# Shruthi-Analog-Polivoks-v01.net
KiCad netlist of a schematic drawn in EAGLE
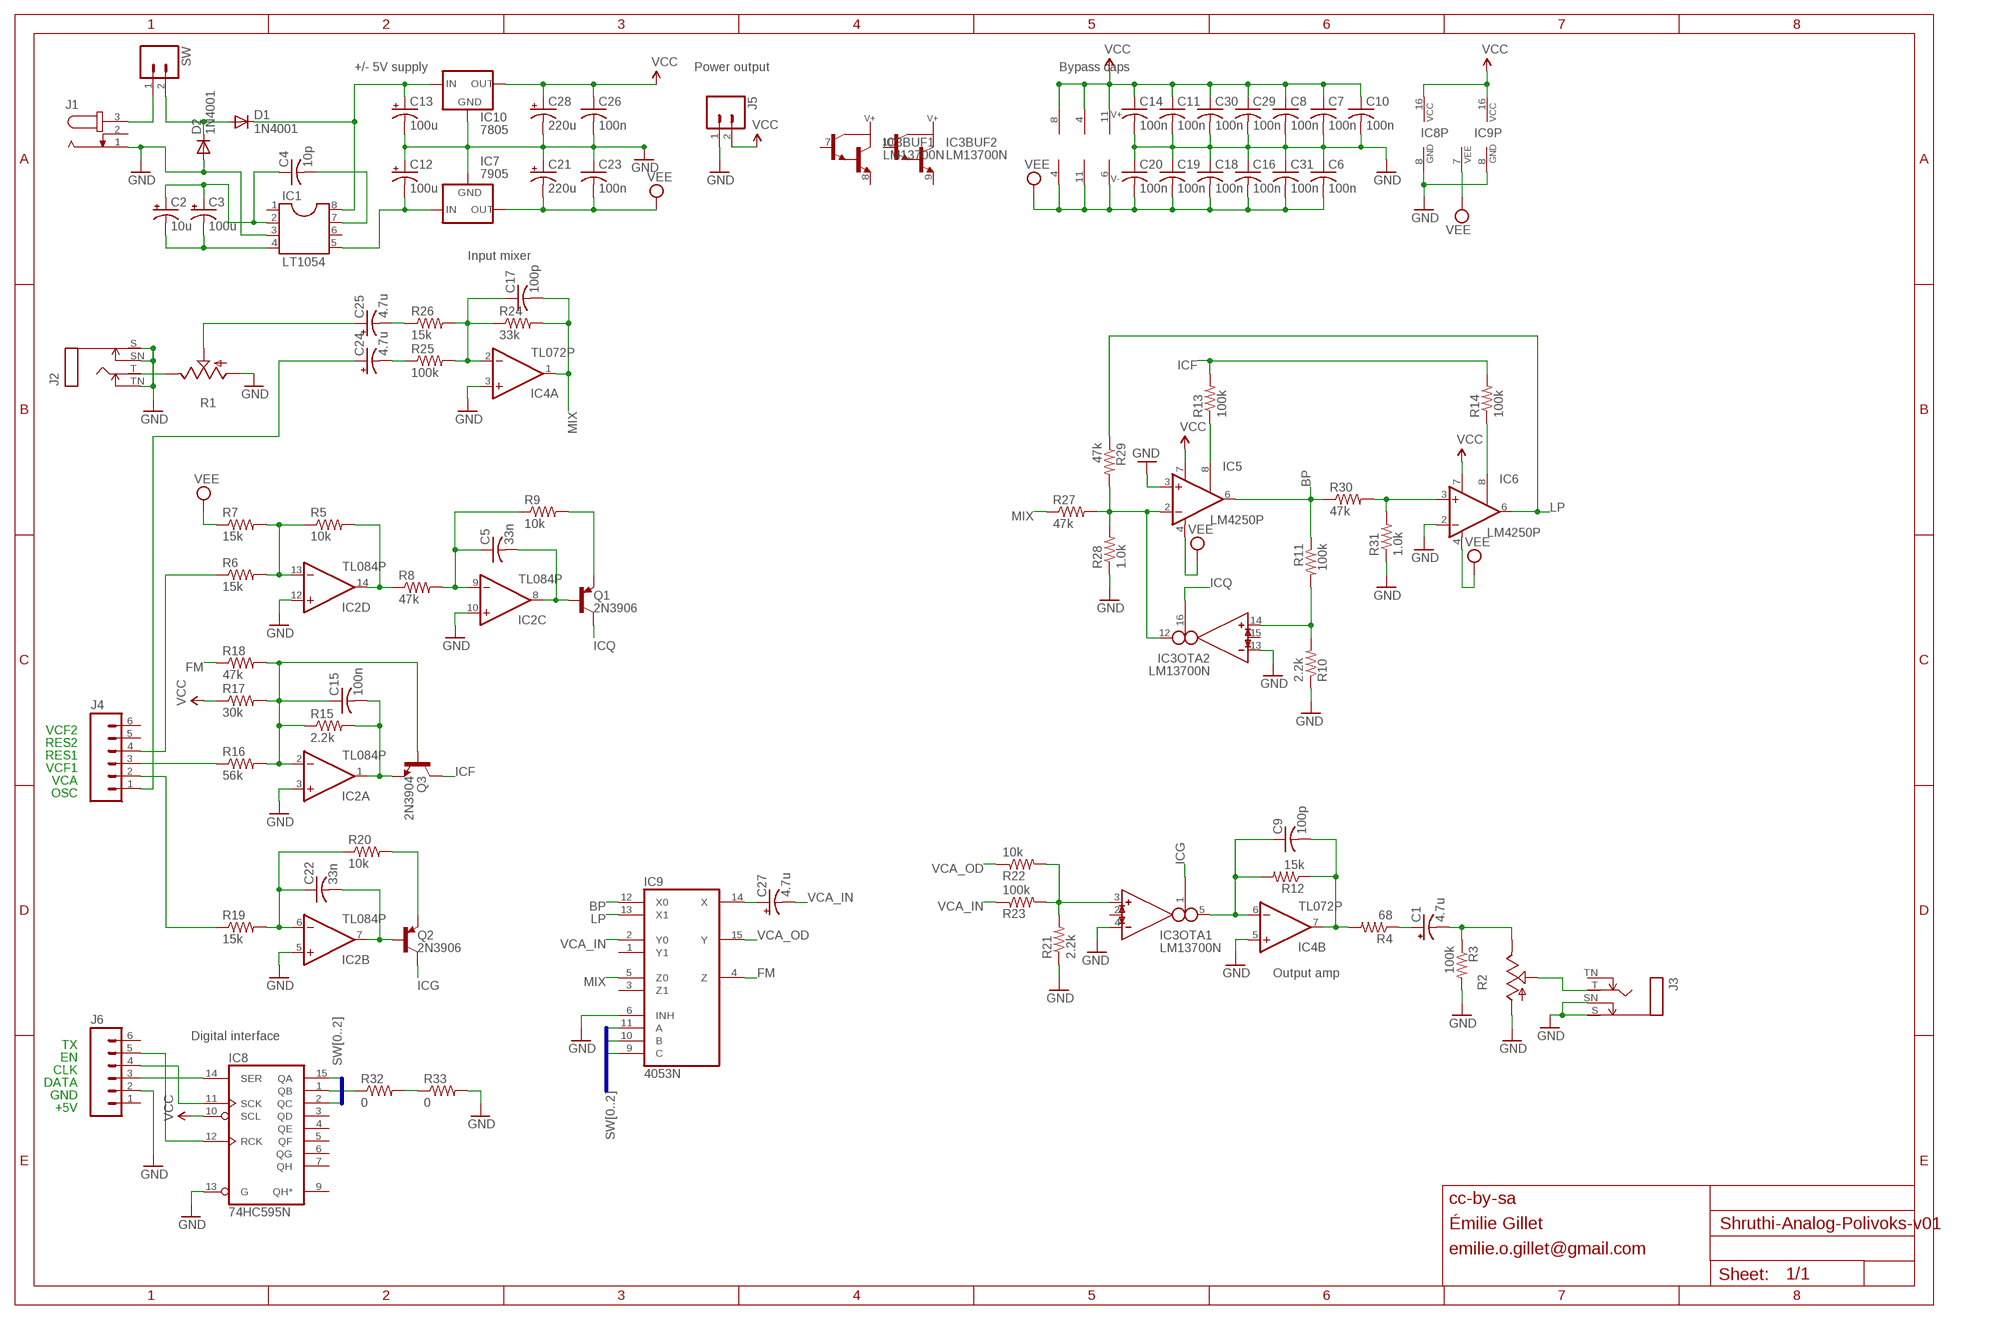
[diagram p0: schematic, sheet 1]

(export (version "E")
  (design (tool "Eeschema 10.0.6"))
  (components
    (comp (ref "C1")
      (value "4.7u")
      (footprint "eagle-import:E2,5-6")
      (libsource (lib "eagle-import") (part "CPOL-USE2.5-6"))
    )
    (comp (ref "C2")
      (value "10u")
      (footprint "eagle-import:E2,5-5")
      (libsource (lib "eagle-import") (part "CPOL-USE2.5-5"))
    )
    (comp (ref "C3")
      (value "100u")
      (footprint "eagle-import:E2,5-6")
      (libsource (lib "eagle-import") (part "CPOL-USE2.5-6"))
    )
    (comp (ref "C4")
      (value "10p")
      (footprint "eagle-import:C025-025X050")
      (libsource (lib "eagle-import") (part "C-US025-025X050"))
    )
    (comp (ref "C5")
      (value "33n")
      (footprint "eagle-import:C050-025X075")
      (libsource (lib "eagle-import") (part "C-US050-025X075"))
    )
    (comp (ref "C6")
      (value "100n")
      (footprint "eagle-import:C025-025X050")
      (libsource (lib "eagle-import") (part "C-US025-025X050"))
    )
    (comp (ref "C7")
      (value "100n")
      (footprint "eagle-import:C025-025X050")
      (libsource (lib "eagle-import") (part "C-US025-025X050"))
    )
    (comp (ref "C8")
      (value "100n")
      (footprint "eagle-import:C025-025X050")
      (libsource (lib "eagle-import") (part "C-US025-025X050"))
    )
    (comp (ref "C9")
      (value "100p")
      (footprint "eagle-import:C025-025X050")
      (libsource (lib "eagle-import") (part "C-US025-025X050"))
    )
    (comp (ref "C10")
      (value "100n")
      (footprint "eagle-import:C025-025X050")
      (libsource (lib "eagle-import") (part "C-US025-025X050"))
    )
    (comp (ref "C11")
      (value "100n")
      (footprint "eagle-import:C025-025X050")
      (libsource (lib "eagle-import") (part "C-US025-025X050"))
    )
    (comp (ref "C12")
      (value "100u")
      (footprint "eagle-import:E2,5-7")
      (libsource (lib "eagle-import") (part "CPOL-USE2.5-7"))
    )
    (comp (ref "C13")
      (value "100u")
      (footprint "eagle-import:E2,5-7")
      (libsource (lib "eagle-import") (part "CPOL-USE2.5-7"))
    )
    (comp (ref "C14")
      (value "100n")
      (footprint "eagle-import:C025-025X050")
      (libsource (lib "eagle-import") (part "C-US025-025X050"))
    )
    (comp (ref "C15")
      (value "100n")
      (footprint "eagle-import:C025-025X050")
      (libsource (lib "eagle-import") (part "C-US025-025X050"))
    )
    (comp (ref "C16")
      (value "100n")
      (footprint "eagle-import:C025-025X050")
      (libsource (lib "eagle-import") (part "C-US025-025X050"))
    )
    (comp (ref "C17")
      (value "100p")
      (footprint "eagle-import:C025-025X050")
      (libsource (lib "eagle-import") (part "C-US025-025X050"))
    )
    (comp (ref "C18")
      (value "100n")
      (footprint "eagle-import:C025-025X050")
      (libsource (lib "eagle-import") (part "C-US025-025X050"))
    )
    (comp (ref "C19")
      (value "100n")
      (footprint "eagle-import:C025-025X050")
      (libsource (lib "eagle-import") (part "C-US025-025X050"))
    )
    (comp (ref "C20")
      (value "100n")
      (footprint "eagle-import:C025-025X050")
      (libsource (lib "eagle-import") (part "C-US025-025X050"))
    )
    (comp (ref "C21")
      (value "220u")
      (footprint "eagle-import:E5-10,5")
      (libsource (lib "eagle-import") (part "CPOL-USE5-10.5"))
    )
    (comp (ref "C22")
      (value "33n")
      (footprint "eagle-import:C050-025X075")
      (libsource (lib "eagle-import") (part "C-US050-025X075"))
    )
    (comp (ref "C23")
      (value "100n")
      (footprint "eagle-import:C025-025X050")
      (libsource (lib "eagle-import") (part "C-US025-025X050"))
    )
    (comp (ref "C24")
      (value "4.7u")
      (footprint "eagle-import:E2,5-6")
      (libsource (lib "eagle-import") (part "CPOL-USE2.5-6"))
    )
    (comp (ref "C25")
      (value "4.7u")
      (footprint "eagle-import:E2,5-6")
      (libsource (lib "eagle-import") (part "CPOL-USE2.5-6"))
    )
    (comp (ref "C26")
      (value "100n")
      (footprint "eagle-import:C025-025X050")
      (libsource (lib "eagle-import") (part "C-US025-025X050"))
    )
    (comp (ref "C27")
      (value "4.7u")
      (footprint "eagle-import:E2,5-6")
      (libsource (lib "eagle-import") (part "CPOL-USE2.5-6"))
    )
    (comp (ref "C28")
      (value "220u")
      (footprint "eagle-import:E5-10,5")
      (libsource (lib "eagle-import") (part "CPOL-USE5-10.5"))
    )
    (comp (ref "C29")
      (value "100n")
      (footprint "eagle-import:C025-025X050")
      (libsource (lib "eagle-import") (part "C-US025-025X050"))
    )
    (comp (ref "C30")
      (value "100n")
      (footprint "eagle-import:C025-025X050")
      (libsource (lib "eagle-import") (part "C-US025-025X050"))
    )
    (comp (ref "C31")
      (value "100n")
      (footprint "eagle-import:C025-025X050")
      (libsource (lib "eagle-import") (part "C-US025-025X050"))
    )
    (comp (ref "D1")
      (value "1N4001")
      (footprint "eagle-import:DO41-10")
      (libsource (lib "eagle-import") (part "1N4004"))
    )
    (comp (ref "D2")
      (value "1N4001")
      (footprint "eagle-import:DO41-10")
      (libsource (lib "eagle-import") (part "1N4004"))
    )
    (comp (ref "IC1")
      (value "LT1054")
      (footprint "eagle-import:DIL08")
      (libsource (lib "eagle-import") (part "DIL8"))
    )
    (comp (ref "IC2")
      (value "TL084P")
      (footprint "eagle-import:DIL14")
      (libsource (lib "eagle-import") (part "TL084P"))
    )
    (comp (ref "IC3")
      (value "LM13700N")
      (footprint "eagle-import:DIL16")
      (libsource (lib "eagle-import") (part "LM13700N"))
    )
    (comp (ref "IC4")
      (value "TL072P")
      (footprint "eagle-import:DIL08")
      (libsource (lib "eagle-import") (part "TL072P"))
    )
    (comp (ref "IC5")
      (value "LM4250P")
      (footprint "eagle-import:DIL08")
      (libsource (lib "eagle-import") (part "LM4250P"))
    )
    (comp (ref "IC6")
      (value "LM4250P")
      (footprint "eagle-import:DIL08")
      (libsource (lib "eagle-import") (part "LM4250P"))
    )
    (comp (ref "IC7")
      (value "7905")
      (footprint "eagle-import:79XXS")
      (libsource (lib "eagle-import") (part "79XXS"))
    )
    (comp (ref "IC8")
      (value "74HC595N")
      (footprint "eagle-import:DIL16")
      (libsource (lib "eagle-import") (part "74595NHC"))
    )
    (comp (ref "IC9")
      (value "4053N")
      (footprint "eagle-import:DIL16")
      (libsource (lib "eagle-import") (part "4053N"))
    )
    (comp (ref "IC10")
      (value "7805")
      (footprint "eagle-import:78XXS")
      (libsource (lib "eagle-import") (part "78XXS"))
    )
    (comp (ref "J1")
      (value "JACK-PLUG2")
      (footprint "eagle-import:SPC4078_BIG_HOLES")
      (libsource (lib "eagle-import") (part "JACK-PLUG2"))
    )
    (comp (ref "J2")
      (value "MONOSWS")
      (footprint "eagle-import:NMJ4HC-S")
      (libsource (lib "eagle-import") (part "MONOSWS"))
    )
    (comp (ref "J3")
      (value "MONOSWS")
      (footprint "eagle-import:NMJ4HC-S")
      (libsource (lib "eagle-import") (part "MONOSWS"))
    )
    (comp (ref "J4")
      (value "M06SIP")
      (footprint "eagle-import:1X06")
      (libsource (lib "eagle-import") (part "M06SIP"))
    )
    (comp (ref "J5")
      (value "M02PTH")
      (footprint "eagle-import:1X02")
      (libsource (lib "eagle-import") (part "M02PTH"))
    )
    (comp (ref "J6")
      (value "M06SIP")
      (footprint "eagle-import:1X06")
      (libsource (lib "eagle-import") (part "M06SIP"))
    )
    (comp (ref "Q1")
      (value "2N3906")
      (footprint "eagle-import:TO92-")
      (libsource (lib "eagle-import") (part "2N3906-"))
    )
    (comp (ref "Q2")
      (value "2N3906")
      (footprint "eagle-import:TO92-")
      (libsource (lib "eagle-import") (part "2N3906-"))
    )
    (comp (ref "Q3")
      (value "2N3904")
      (footprint "eagle-import:TO92-")
      (libsource (lib "eagle-import") (part "2N3904"))
    )
    (comp (ref "R1")
      (value "POT_USCABLED")
      (footprint "eagle-import:CABLE_POT_6MM")
      (libsource (lib "eagle-import") (part "POT_USCABLED"))
    )
    (comp (ref "R2")
      (value "POT_USCABLED")
      (footprint "eagle-import:CABLE_POT_6MM")
      (libsource (lib "eagle-import") (part "POT_USCABLED"))
    )
    (comp (ref "R3")
      (value "100k")
      (footprint "eagle-import:0204_7")
      (libsource (lib "eagle-import") (part "R-US_0204/7"))
    )
    (comp (ref "R4")
      (value "68")
      (footprint "eagle-import:0204_7")
      (libsource (lib "eagle-import") (part "R-US_0204/7"))
    )
    (comp (ref "R5")
      (value "10k")
      (footprint "eagle-import:0204_7")
      (libsource (lib "eagle-import") (part "R-US_0204/7"))
    )
    (comp (ref "R6")
      (value "15k")
      (footprint "eagle-import:0204_7")
      (libsource (lib "eagle-import") (part "R-US_0204/7"))
    )
    (comp (ref "R7")
      (value "15k")
      (footprint "eagle-import:0204_7")
      (libsource (lib "eagle-import") (part "R-US_0204/7"))
    )
    (comp (ref "R8")
      (value "47k")
      (footprint "eagle-import:0204_7")
      (libsource (lib "eagle-import") (part "R-US_0204/7"))
    )
    (comp (ref "R9")
      (value "10k")
      (footprint "eagle-import:0204_7")
      (libsource (lib "eagle-import") (part "R-US_0204/7"))
    )
    (comp (ref "R10")
      (value "2.2k")
      (footprint "eagle-import:0204_7")
      (libsource (lib "eagle-import") (part "R-US_0204/7"))
    )
    (comp (ref "R11")
      (value "100k")
      (footprint "eagle-import:0204_7")
      (libsource (lib "eagle-import") (part "R-US_0204/7"))
    )
    (comp (ref "R12")
      (value "15k")
      (footprint "eagle-import:0204_7")
      (libsource (lib "eagle-import") (part "R-US_0204/7"))
    )
    (comp (ref "R13")
      (value "100k")
      (footprint "eagle-import:0204_7")
      (libsource (lib "eagle-import") (part "R-US_0204/7"))
    )
    (comp (ref "R14")
      (value "100k")
      (footprint "eagle-import:0204_7")
      (libsource (lib "eagle-import") (part "R-US_0204/7"))
    )
    (comp (ref "R15")
      (value "2.2k")
      (footprint "eagle-import:0204_7")
      (libsource (lib "eagle-import") (part "R-US_0204/7"))
    )
    (comp (ref "R16")
      (value "56k")
      (footprint "eagle-import:0204_7")
      (libsource (lib "eagle-import") (part "R-US_0204/7"))
    )
    (comp (ref "R17")
      (value "30k")
      (footprint "eagle-import:0204_7")
      (libsource (lib "eagle-import") (part "R-US_0204/7"))
    )
    (comp (ref "R18")
      (value "47k")
      (footprint "eagle-import:0204_7")
      (libsource (lib "eagle-import") (part "R-US_0204/7"))
    )
    (comp (ref "R19")
      (value "15k")
      (footprint "eagle-import:0204_7")
      (libsource (lib "eagle-import") (part "R-US_0204/7"))
    )
    (comp (ref "R20")
      (value "10k")
      (footprint "eagle-import:0204_7")
      (libsource (lib "eagle-import") (part "R-US_0204/7"))
    )
    (comp (ref "R21")
      (value "2.2k")
      (footprint "eagle-import:0204_7")
      (libsource (lib "eagle-import") (part "R-US_0204/7"))
    )
    (comp (ref "R22")
      (value "10k")
      (footprint "eagle-import:0204_7")
      (libsource (lib "eagle-import") (part "R-US_0204/7"))
    )
    (comp (ref "R23")
      (value "100k")
      (footprint "eagle-import:0204_7")
      (libsource (lib "eagle-import") (part "R-US_0204/7"))
    )
    (comp (ref "R24")
      (value "33k")
      (footprint "eagle-import:0204_7")
      (libsource (lib "eagle-import") (part "R-US_0204/7"))
    )
    (comp (ref "R25")
      (value "100k")
      (footprint "eagle-import:0204_7")
      (libsource (lib "eagle-import") (part "R-US_0204/7"))
    )
    (comp (ref "R26")
      (value "15k")
      (footprint "eagle-import:0204_7")
      (libsource (lib "eagle-import") (part "R-US_0204/7"))
    )
    (comp (ref "R27")
      (value "47k")
      (footprint "eagle-import:0204_7")
      (libsource (lib "eagle-import") (part "R-US_0204/7"))
    )
    (comp (ref "R28")
      (value "1.0k")
      (footprint "eagle-import:0204_7")
      (libsource (lib "eagle-import") (part "R-US_0204/7"))
    )
    (comp (ref "R29")
      (value "47k")
      (footprint "eagle-import:0204_7")
      (libsource (lib "eagle-import") (part "R-US_0204/7"))
    )
    (comp (ref "R30")
      (value "47k")
      (footprint "eagle-import:0204_7")
      (libsource (lib "eagle-import") (part "R-US_0204/7"))
    )
    (comp (ref "R31")
      (value "1.0k")
      (footprint "eagle-import:0204_7")
      (libsource (lib "eagle-import") (part "R-US_0204/7"))
    )
    (comp (ref "R32")
      (value "0")
      (footprint "eagle-import:0204V")
      (libsource (lib "eagle-import") (part "R-US_0204/2V"))
    )
    (comp (ref "R33")
      (value "0")
      (footprint "eagle-import:0204V")
      (libsource (lib "eagle-import") (part "R-US_0204/2V"))
    )
    (comp (ref "SW")
      (value "M02PTH")
      (footprint "eagle-import:1X02")
      (libsource (lib "eagle-import") (part "M02PTH"))
    )
  )
  (nets
    (net (code "1") (name "/BP") (class "Default")
      (node (ref "IC5") (pin "6") (pinfunction "OUT_6") (pintype "output"))
      (node (ref "IC9") (pin "12") (pinfunction "X0_12") (pintype "bidirectional"))
      (node (ref "R11") (pin "1") (pinfunction "1_1") (pintype "passive"))
      (node (ref "R30") (pin "1") (pinfunction "1_1") (pintype "passive"))
    )
    (net (code "2") (name "/FM") (class "Default")
      (node (ref "IC9") (pin "4") (pinfunction "Z_4") (pintype "bidirectional"))
      (node (ref "R18") (pin "1") (pinfunction "1_1") (pintype "passive"))
    )
    (net (code "3") (name "/ICF") (class "Default")
      (node (ref "Q3") (pin "1") (pinfunction "C_1") (pintype "passive"))
      (node (ref "R13") (pin "2") (pinfunction "2_2") (pintype "passive"))
      (node (ref "R14") (pin "2") (pinfunction "2_2") (pintype "passive"))
    )
    (net (code "4") (name "/ICG") (class "Default")
      (node (ref "IC3") (pin "1") (pinfunction "I_BIAS_1") (pintype "input"))
      (node (ref "Q2") (pin "1") (pinfunction "C_1") (pintype "passive"))
    )
    (net (code "5") (name "/ICQ") (class "Default")
      (node (ref "IC3") (pin "16") (pinfunction "I_BIAS_16") (pintype "input"))
      (node (ref "Q1") (pin "1") (pinfunction "C_1") (pintype "passive"))
    )
    (net (code "6") (name "/LP") (class "Default")
      (node (ref "IC6") (pin "6") (pinfunction "OUT_6") (pintype "output"))
      (node (ref "IC9") (pin "13") (pinfunction "X1_13") (pintype "bidirectional"))
      (node (ref "R29") (pin "1") (pinfunction "1_1") (pintype "passive"))
    )
    (net (code "7") (name "/MIX") (class "Default")
      (node (ref "C17") (pin "2") (pinfunction "2_2") (pintype "passive"))
      (node (ref "IC4") (pin "1") (pinfunction "OUT_1") (pintype "output"))
      (node (ref "IC9") (pin "5") (pinfunction "Z0_5") (pintype "bidirectional"))
      (node (ref "R24") (pin "2") (pinfunction "2_2") (pintype "passive"))
      (node (ref "R27") (pin "1") (pinfunction "1_1") (pintype "passive"))
    )
    (net (code "8") (name "/SW0") (class "Default")
      (node (ref "IC8") (pin "15") (pinfunction "QA_15") (pintype "tri_state"))
      (node (ref "IC9") (pin "9") (pinfunction "C_9") (pintype "input"))
    )
    (net (code "9") (name "/SW1") (class "Default")
      (node (ref "IC8") (pin "1") (pinfunction "QB_1") (pintype "tri_state"))
      (node (ref "IC9") (pin "10") (pinfunction "B_10") (pintype "input"))
      (node (ref "R32") (pin "1") (pinfunction "1_1") (pintype "passive"))
    )
    (net (code "10") (name "/SW2") (class "Default")
      (node (ref "IC8") (pin "2") (pinfunction "QC_2") (pintype "tri_state"))
      (node (ref "IC9") (pin "11") (pinfunction "A_11") (pintype "input"))
    )
    (net (code "12") (name "/VCA_IN") (class "Default")
      (node (ref "C27") (pin "-") (pinfunction "-_-") (pintype "passive"))
      (node (ref "IC9") (pin "2") (pinfunction "Y0_2") (pintype "bidirectional"))
      (node (ref "R23") (pin "1") (pinfunction "1_1") (pintype "passive"))
    )
    (net (code "13") (name "/VCA_OD") (class "Default")
      (node (ref "IC9") (pin "15") (pinfunction "Y_15") (pintype "bidirectional"))
      (node (ref "R22") (pin "1") (pinfunction "1_1") (pintype "passive"))
    )
    (net (code "14") (name "GND") (class "Default")
      (node (ref "C10") (pin "2") (pinfunction "2_2") (pintype "passive"))
      (node (ref "C11") (pin "2") (pinfunction "2_2") (pintype "passive"))
      (node (ref "C12") (pin "+") (pinfunction "+_+") (pintype "passive"))
      (node (ref "C13") (pin "-") (pinfunction "-_-") (pintype "passive"))
      (node (ref "C14") (pin "2") (pinfunction "2_2") (pintype "passive"))
      (node (ref "C16") (pin "1") (pinfunction "1_1") (pintype "passive"))
      (node (ref "C18") (pin "1") (pinfunction "1_1") (pintype "passive"))
      (node (ref "C19") (pin "1") (pinfunction "1_1") (pintype "passive"))
      (node (ref "C20") (pin "1") (pinfunction "1_1") (pintype "passive"))
      (node (ref "C21") (pin "+") (pinfunction "+_+") (pintype "passive"))
      (node (ref "C23") (pin "1") (pinfunction "1_1") (pintype "passive"))
      (node (ref "C26") (pin "2") (pinfunction "2_2") (pintype "passive"))
      (node (ref "C28") (pin "-") (pinfunction "-_-") (pintype "passive"))
      (node (ref "C29") (pin "2") (pinfunction "2_2") (pintype "passive"))
      (node (ref "C30") (pin "2") (pinfunction "2_2") (pintype "passive"))
      (node (ref "C31") (pin "1") (pinfunction "1_1") (pintype "passive"))
      (node (ref "C6") (pin "1") (pinfunction "1_1") (pintype "passive"))
      (node (ref "C7") (pin "2") (pinfunction "2_2") (pintype "passive"))
      (node (ref "C8") (pin "2") (pinfunction "2_2") (pintype "passive"))
      (node (ref "D2") (pin "A") (pinfunction "A_A") (pintype "passive"))
      (node (ref "IC1") (pin "3") (pinfunction "3_3") (pintype "passive"))
      (node (ref "IC10") (pin "GND") (pinfunction "GND_GND") (pintype "input"))
      (node (ref "IC2") (pin "10") (pinfunction "+IN_10") (pintype "input"))
      (node (ref "IC2") (pin "12") (pinfunction "+IN_12") (pintype "input"))
      (node (ref "IC2") (pin "3") (pinfunction "+IN_3") (pintype "input"))
      (node (ref "IC2") (pin "5") (pinfunction "+IN_5") (pintype "input"))
      (node (ref "IC3") (pin "13") (pinfunction "IN_N_13") (pintype "input"))
      (node (ref "IC3") (pin "4") (pinfunction "IN_N_4") (pintype "input"))
      (node (ref "IC4") (pin "3") (pinfunction "+IN_3") (pintype "input"))
      (node (ref "IC4") (pin "5") (pinfunction "+IN_5") (pintype "input"))
      (node (ref "IC5") (pin "3") (pinfunction "+IN_3") (pintype "input"))
      (node (ref "IC6") (pin "2") (pinfunction "-IN_2") (pintype "input"))
      (node (ref "IC7") (pin "GND") (pinfunction "GND_GND") (pintype "input"))
      (node (ref "IC8") (pin "13") (pinfunction "G_13") (pintype "input"))
      (node (ref "IC8") (pin "8") (pinfunction "GND_8") (pintype "power_in"))
      (node (ref "IC9") (pin "6") (pinfunction "INH_6") (pintype "input"))
      (node (ref "IC9") (pin "8") (pinfunction "GND_8") (pintype "power_in"))
      (node (ref "J1") (pin "1") (pinfunction "1_1") (pintype "passive"))
      (node (ref "J2") (pin "S") (pinfunction "S_S") (pintype "passive"))
      (node (ref "J2") (pin "SN") (pinfunction "SN_SN") (pintype "passive"))
      (node (ref "J2") (pin "TN") (pinfunction "TN_TN") (pintype "passive"))
      (node (ref "J3") (pin "S") (pinfunction "S_S") (pintype "passive"))
      (node (ref "J3") (pin "SN") (pinfunction "SN_SN") (pintype "passive"))
      (node (ref "J5") (pin "1") (pinfunction "1_1") (pintype "passive"))
      (node (ref "J6") (pin "2") (pinfunction "2_2") (pintype "passive"))
      (node (ref "R1") (pin "A") (pinfunction "A_A") (pintype "passive"))
      (node (ref "R10") (pin "1") (pinfunction "1_1") (pintype "passive"))
      (node (ref "R2") (pin "A") (pinfunction "A_A") (pintype "passive"))
      (node (ref "R21") (pin "1") (pinfunction "1_1") (pintype "passive"))
      (node (ref "R28") (pin "1") (pinfunction "1_1") (pintype "passive"))
      (node (ref "R3") (pin "2") (pinfunction "2_2") (pintype "passive"))
      (node (ref "R31") (pin "1") (pinfunction "1_1") (pintype "passive"))
      (node (ref "R33") (pin "2") (pinfunction "2_2") (pintype "passive"))
    )
    (net (code "15") (name "Net-(C1-Pad+)") (class "Default")
      (node (ref "C1") (pin "+") (pinfunction "+_+") (pintype "passive"))
      (node (ref "R4") (pin "1") (pinfunction "1_1") (pintype "passive"))
    )
    (net (code "16") (name "Net-(C1-Pad-)") (class "Default")
      (node (ref "C1") (pin "-") (pinfunction "-_-") (pintype "passive"))
      (node (ref "R2") (pin "E") (pinfunction "E_E") (pintype "passive"))
      (node (ref "R3") (pin "1") (pinfunction "1_1") (pintype "passive"))
    )
    (net (code "17") (name "Net-(C2-Pad+)") (class "Default")
      (node (ref "C2") (pin "+") (pinfunction "+_+") (pintype "passive"))
      (node (ref "C3") (pin "+") (pinfunction "+_+") (pintype "passive"))
      (node (ref "C4") (pin "1") (pinfunction "1_1") (pintype "passive"))
      (node (ref "IC1") (pin "2") (pinfunction "2_2") (pintype "passive"))
    )
    (net (code "18") (name "Net-(C2-Pad-)") (class "Default")
      (node (ref "C2") (pin "-") (pinfunction "-_-") (pintype "passive"))
      (node (ref "C3") (pin "-") (pinfunction "-_-") (pintype "passive"))
      (node (ref "IC1") (pin "4") (pinfunction "4_4") (pintype "passive"))
    )
    (net (code "19") (name "Net-(C4-Pad2)") (class "Default")
      (node (ref "C4") (pin "2") (pinfunction "2_2") (pintype "passive"))
      (node (ref "IC1") (pin "7") (pinfunction "7_7") (pintype "passive"))
    )
    (net (code "20") (name "Net-(C12-Pad-)") (class "Default")
      (node (ref "C12") (pin "-") (pinfunction "-_-") (pintype "passive"))
      (node (ref "IC1") (pin "5") (pinfunction "5_5") (pintype "passive"))
      (node (ref "IC7") (pin "IN") (pinfunction "IN_IN") (pintype "input"))
    )
    (net (code "21") (name "Net-(C13-Pad+)") (class "Default")
      (node (ref "C13") (pin "+") (pinfunction "+_+") (pintype "passive"))
      (node (ref "D1") (pin "C") (pinfunction "C_C") (pintype "passive"))
      (node (ref "IC1") (pin "8") (pinfunction "8_8") (pintype "passive"))
      (node (ref "IC10") (pin "IN") (pinfunction "IN_IN") (pintype "input"))
    )
    (net (code "22") (name "Net-(C24-Pad+)") (class "Default")
      (node (ref "C24") (pin "+") (pinfunction "+_+") (pintype "passive"))
      (node (ref "J4") (pin "1") (pinfunction "1_1") (pintype "passive"))
    )
    (net (code "23") (name "Net-(C24-Pad-)") (class "Default")
      (node (ref "C24") (pin "-") (pinfunction "-_-") (pintype "passive"))
      (node (ref "R25") (pin "1") (pinfunction "1_1") (pintype "passive"))
    )
    (net (code "24") (name "Net-(C25-Pad+)") (class "Default")
      (node (ref "C25") (pin "+") (pinfunction "+_+") (pintype "passive"))
      (node (ref "R1") (pin "S") (pinfunction "S_S") (pintype "passive"))
    )
    (net (code "25") (name "Net-(C25-Pad-)") (class "Default")
      (node (ref "C25") (pin "-") (pinfunction "-_-") (pintype "passive"))
      (node (ref "R26") (pin "1") (pinfunction "1_1") (pintype "passive"))
    )
    (net (code "26") (name "Net-(D1-PadA)") (class "Default")
      (node (ref "D1") (pin "A") (pinfunction "A_A") (pintype "passive"))
      (node (ref "D2") (pin "C") (pinfunction "C_C") (pintype "passive"))
      (node (ref "SW") (pin "2") (pinfunction "2_2") (pintype "passive"))
    )
    (net (code "27") (name "Net-(IC2A--IN)") (class "Default")
      (node (ref "C15") (pin "1") (pinfunction "1_1") (pintype "passive"))
      (node (ref "IC2") (pin "2") (pinfunction "-IN_2") (pintype "input"))
      (node (ref "Q3") (pin "2") (pinfunction "B_2") (pintype "passive"))
      (node (ref "R15") (pin "1") (pinfunction "1_1") (pintype "passive"))
      (node (ref "R16") (pin "2") (pinfunction "2_2") (pintype "passive"))
      (node (ref "R17") (pin "2") (pinfunction "2_2") (pintype "passive"))
      (node (ref "R18") (pin "2") (pinfunction "2_2") (pintype "passive"))
    )
    (net (code "28") (name "Net-(IC2A-OUT)") (class "Default")
      (node (ref "C15") (pin "2") (pinfunction "2_2") (pintype "passive"))
      (node (ref "IC2") (pin "1") (pinfunction "OUT_1") (pintype "output"))
      (node (ref "Q3") (pin "3") (pinfunction "E_3") (pintype "passive"))
      (node (ref "R15") (pin "2") (pinfunction "2_2") (pintype "passive"))
    )
    (net (code "29") (name "Net-(IC2B--IN)") (class "Default")
      (node (ref "C22") (pin "1") (pinfunction "1_1") (pintype "passive"))
      (node (ref "IC2") (pin "6") (pinfunction "-IN_6") (pintype "input"))
      (node (ref "R19") (pin "2") (pinfunction "2_2") (pintype "passive"))
      (node (ref "R20") (pin "1") (pinfunction "1_1") (pintype "passive"))
    )
    (net (code "30") (name "Net-(IC2B-OUT)") (class "Default")
      (node (ref "C22") (pin "2") (pinfunction "2_2") (pintype "passive"))
      (node (ref "IC2") (pin "7") (pinfunction "OUT_7") (pintype "output"))
      (node (ref "Q2") (pin "2") (pinfunction "B_2") (pintype "passive"))
    )
    (net (code "31") (name "Net-(IC2C--IN)") (class "Default")
      (node (ref "C5") (pin "1") (pinfunction "1_1") (pintype "passive"))
      (node (ref "IC2") (pin "9") (pinfunction "-IN_9") (pintype "input"))
      (node (ref "R8") (pin "2") (pinfunction "2_2") (pintype "passive"))
      (node (ref "R9") (pin "1") (pinfunction "1_1") (pintype "passive"))
    )
    (net (code "32") (name "Net-(IC2C-OUT)") (class "Default")
      (node (ref "C5") (pin "2") (pinfunction "2_2") (pintype "passive"))
      (node (ref "IC2") (pin "8") (pinfunction "OUT_8") (pintype "output"))
      (node (ref "Q1") (pin "2") (pinfunction "B_2") (pintype "passive"))
    )
    (net (code "33") (name "Net-(IC2D--IN)") (class "Default")
      (node (ref "IC2") (pin "13") (pinfunction "-IN_13") (pintype "input"))
      (node (ref "R5") (pin "1") (pinfunction "1_1") (pintype "passive"))
      (node (ref "R6") (pin "2") (pinfunction "2_2") (pintype "passive"))
      (node (ref "R7") (pin "2") (pinfunction "2_2") (pintype "passive"))
    )
    (net (code "34") (name "Net-(IC2D-OUT)") (class "Default")
      (node (ref "IC2") (pin "14") (pinfunction "OUT_14") (pintype "output"))
      (node (ref "R5") (pin "2") (pinfunction "2_2") (pintype "passive"))
      (node (ref "R8") (pin "1") (pinfunction "1_1") (pintype "passive"))
    )
    (net (code "35") (name "Net-(IC3C-IN_P)") (class "Default")
      (node (ref "IC3") (pin "3") (pinfunction "IN_P_3") (pintype "input"))
      (node (ref "R21") (pin "2") (pinfunction "2_2") (pintype "passive"))
      (node (ref "R22") (pin "2") (pinfunction "2_2") (pintype "passive"))
      (node (ref "R23") (pin "2") (pinfunction "2_2") (pintype "passive"))
    )
    (net (code "36") (name "Net-(IC3C-OUT)") (class "Default")
      (node (ref "C9") (pin "1") (pinfunction "1_1") (pintype "passive"))
      (node (ref "IC3") (pin "5") (pinfunction "OUT_5") (pintype "output"))
      (node (ref "IC4") (pin "6") (pinfunction "-IN_6") (pintype "input"))
      (node (ref "R12") (pin "2") (pinfunction "2_2") (pintype "passive"))
    )
    (net (code "37") (name "Net-(IC3D-IN_P)") (class "Default")
      (node (ref "IC3") (pin "14") (pinfunction "IN_P_14") (pintype "input"))
      (node (ref "R10") (pin "2") (pinfunction "2_2") (pintype "passive"))
      (node (ref "R11") (pin "2") (pinfunction "2_2") (pintype "passive"))
    )
    (net (code "38") (name "Net-(IC3D-OUT)") (class "Default")
      (node (ref "IC3") (pin "12") (pinfunction "OUT_12") (pintype "output"))
      (node (ref "IC5") (pin "2") (pinfunction "-IN_2") (pintype "input"))
      (node (ref "R27") (pin "2") (pinfunction "2_2") (pintype "passive"))
      (node (ref "R28") (pin "2") (pinfunction "2_2") (pintype "passive"))
      (node (ref "R29") (pin "2") (pinfunction "2_2") (pintype "passive"))
    )
    (net (code "39") (name "Net-(IC4A--IN)") (class "Default")
      (node (ref "C17") (pin "1") (pinfunction "1_1") (pintype "passive"))
      (node (ref "IC4") (pin "2") (pinfunction "-IN_2") (pintype "input"))
      (node (ref "R24") (pin "1") (pinfunction "1_1") (pintype "passive"))
      (node (ref "R25") (pin "2") (pinfunction "2_2") (pintype "passive"))
      (node (ref "R26") (pin "2") (pinfunction "2_2") (pintype "passive"))
    )
    (net (code "40") (name "Net-(IC4B-OUT)") (class "Default")
      (node (ref "C9") (pin "2") (pinfunction "2_2") (pintype "passive"))
      (node (ref "IC4") (pin "7") (pinfunction "OUT_7") (pintype "output"))
      (node (ref "R12") (pin "1") (pinfunction "1_1") (pintype "passive"))
      (node (ref "R4") (pin "2") (pinfunction "2_2") (pintype "passive"))
    )
    (net (code "41") (name "Net-(IC5-ISET)") (class "Default")
      (node (ref "IC5") (pin "8") (pinfunction "ISET_8") (pintype "passive"))
      (node (ref "R13") (pin "1") (pinfunction "1_1") (pintype "passive"))
    )
    (net (code "42") (name "Net-(IC6-+IN)") (class "Default")
      (node (ref "IC6") (pin "3") (pinfunction "+IN_3") (pintype "input"))
      (node (ref "R30") (pin "2") (pinfunction "2_2") (pintype "passive"))
      (node (ref "R31") (pin "2") (pinfunction "2_2") (pintype "passive"))
    )
    (net (code "43") (name "Net-(IC6-ISET)") (class "Default")
      (node (ref "IC6") (pin "8") (pinfunction "ISET_8") (pintype "passive"))
      (node (ref "R14") (pin "1") (pinfunction "1_1") (pintype "passive"))
    )
    (net (code "44") (name "Net-(IC8A-RCK)") (class "Default")
      (node (ref "IC8") (pin "12") (pinfunction "RCK_12") (pintype "input"))
      (node (ref "J6") (pin "5") (pinfunction "5_5") (pintype "passive"))
    )
    (net (code "45") (name "Net-(IC8A-SCK)") (class "Default")
      (node (ref "IC8") (pin "11") (pinfunction "SCK_11") (pintype "input"))
      (node (ref "J6") (pin "4") (pinfunction "4_4") (pintype "passive"))
    )
    (net (code "46") (name "Net-(IC8A-SER)") (class "Default")
      (node (ref "IC8") (pin "14") (pinfunction "SER_14") (pintype "input"))
      (node (ref "J6") (pin "3") (pinfunction "3_3") (pintype "passive"))
    )
    (net (code "47") (name "Net-(IC9A-X)") (class "Default")
      (node (ref "C27") (pin "+") (pinfunction "+_+") (pintype "passive"))
      (node (ref "IC9") (pin "14") (pinfunction "X_14") (pintype "bidirectional"))
    )
    (net (code "48") (name "Net-(J1-Pad3)") (class "Default")
      (node (ref "J1") (pin "3") (pinfunction "3_3") (pintype "passive"))
      (node (ref "SW") (pin "1") (pinfunction "1_1") (pintype "passive"))
    )
    (net (code "49") (name "Net-(J2-PadT)") (class "Default")
      (node (ref "J2") (pin "T") (pinfunction "T_T") (pintype "passive"))
      (node (ref "R1") (pin "E") (pinfunction "E_E") (pintype "passive"))
    )
    (net (code "50") (name "Net-(J3-PadT)") (class "Default")
      (node (ref "J3") (pin "T") (pinfunction "T_T") (pintype "passive"))
      (node (ref "R2") (pin "S") (pinfunction "S_S") (pintype "passive"))
    )
    (net (code "51") (name "Net-(J4-Pad2)") (class "Default")
      (node (ref "J4") (pin "2") (pinfunction "2_2") (pintype "passive"))
      (node (ref "R19") (pin "1") (pinfunction "1_1") (pintype "passive"))
    )
    (net (code "52") (name "Net-(J4-Pad3)") (class "Default")
      (node (ref "J4") (pin "3") (pinfunction "3_3") (pintype "passive"))
      (node (ref "R16") (pin "1") (pinfunction "1_1") (pintype "passive"))
    )
    (net (code "53") (name "Net-(J4-Pad4)") (class "Default")
      (node (ref "J4") (pin "4") (pinfunction "4_4") (pintype "passive"))
      (node (ref "R6") (pin "1") (pinfunction "1_1") (pintype "passive"))
    )
    (net (code "54") (name "Net-(Q1-E)") (class "Default")
      (node (ref "Q1") (pin "3") (pinfunction "E_3") (pintype "passive"))
      (node (ref "R9") (pin "2") (pinfunction "2_2") (pintype "passive"))
    )
    (net (code "55") (name "Net-(Q2-E)") (class "Default")
      (node (ref "Q2") (pin "3") (pinfunction "E_3") (pintype "passive"))
      (node (ref "R20") (pin "2") (pinfunction "2_2") (pintype "passive"))
    )
    (net (code "56") (name "Net-(R32-Pad2)") (class "Default")
      (node (ref "R32") (pin "2") (pinfunction "2_2") (pintype "passive"))
      (node (ref "R33") (pin "1") (pinfunction "1_1") (pintype "passive"))
    )
    (net (code "57") (name "VCC") (class "Default")
      (node (ref "C10") (pin "1") (pinfunction "1_1") (pintype "passive"))
      (node (ref "C11") (pin "1") (pinfunction "1_1") (pintype "passive"))
      (node (ref "C14") (pin "1") (pinfunction "1_1") (pintype "passive"))
      (node (ref "C26") (pin "1") (pinfunction "1_1") (pintype "passive"))
      (node (ref "C28") (pin "+") (pinfunction "+_+") (pintype "passive"))
      (node (ref "C29") (pin "1") (pinfunction "1_1") (pintype "passive"))
      (node (ref "C30") (pin "1") (pinfunction "1_1") (pintype "passive"))
      (node (ref "C7") (pin "1") (pinfunction "1_1") (pintype "passive"))
      (node (ref "C8") (pin "1") (pinfunction "1_1") (pintype "passive"))
      (node (ref "IC10") (pin "OUT") (pinfunction "OUT_OUT") (pintype "passive"))
      (node (ref "IC2") (pin "4") (pinfunction "V+_4") (pintype "power_in"))
      (node (ref "IC3") (pin "11") (pinfunction "V+_11") (pintype "power_in"))
      (node (ref "IC4") (pin "8") (pinfunction "V+_8") (pintype "power_in"))
      (node (ref "IC5") (pin "7") (pinfunction "V+_7") (pintype "power_in"))
      (node (ref "IC6") (pin "7") (pinfunction "V+_7") (pintype "power_in"))
      (node (ref "IC8") (pin "10") (pinfunction "SCL_10") (pintype "input"))
      (node (ref "IC8") (pin "16") (pinfunction "VCC_16") (pintype "power_in"))
      (node (ref "IC9") (pin "16") (pinfunction "VCC_16") (pintype "power_in"))
      (node (ref "J5") (pin "2") (pinfunction "2_2") (pintype "passive"))
      (node (ref "R17") (pin "1") (pinfunction "1_1") (pintype "passive"))
    )
    (net (code "58") (name "VEE") (class "Default")
      (node (ref "C16") (pin "2") (pinfunction "2_2") (pintype "passive"))
      (node (ref "C18") (pin "2") (pinfunction "2_2") (pintype "passive"))
      (node (ref "C19") (pin "2") (pinfunction "2_2") (pintype "passive"))
      (node (ref "C20") (pin "2") (pinfunction "2_2") (pintype "passive"))
      (node (ref "C21") (pin "-") (pinfunction "-_-") (pintype "passive"))
      (node (ref "C23") (pin "2") (pinfunction "2_2") (pintype "passive"))
      (node (ref "C31") (pin "2") (pinfunction "2_2") (pintype "passive"))
      (node (ref "C6") (pin "2") (pinfunction "2_2") (pintype "passive"))
      (node (ref "IC2") (pin "11") (pinfunction "V-_11") (pintype "power_in"))
      (node (ref "IC3") (pin "6") (pinfunction "V-_6") (pintype "power_in"))
      (node (ref "IC4") (pin "4") (pinfunction "V-_4") (pintype "power_in"))
      (node (ref "IC5") (pin "4") (pinfunction "V-_4") (pintype "power_in"))
      (node (ref "IC6") (pin "4") (pinfunction "V-_4") (pintype "power_in"))
      (node (ref "IC7") (pin "OUT") (pinfunction "OUT_OUT") (pintype "passive"))
      (node (ref "IC9") (pin "7") (pinfunction "VEE_7") (pintype "power_in"))
      (node (ref "R7") (pin "1") (pinfunction "1_1") (pintype "passive"))
    )
    (net (code "59") (name "unconnected-(IC1-Pad1)") (class "Default")
      (node (ref "IC1") (pin "1") (pinfunction "1_1") (pintype "passive"))
    )
    (net (code "60") (name "unconnected-(IC1-Pad6)") (class "Default")
      (node (ref "IC1") (pin "6") (pinfunction "6_6") (pintype "passive"))
    )
    (net (code "61") (name "unconnected-(IC3A-B-Pad7)") (class "Default")
      (node (ref "IC3") (pin "7") (pinfunction "B_7") (pintype "passive"))
    )
    (net (code "62") (name "unconnected-(IC3A-E-Pad8)") (class "Default")
      (node (ref "IC3") (pin "8") (pinfunction "E_8") (pintype "passive"))
    )
    (net (code "63") (name "unconnected-(IC3B-B-Pad10)") (class "Default")
      (node (ref "IC3") (pin "10") (pinfunction "B_10") (pintype "passive"))
    )
    (net (code "64") (name "unconnected-(IC3B-E-Pad9)") (class "Default")
      (node (ref "IC3") (pin "9") (pinfunction "E_9") (pintype "passive"))
    )
    (net (code "65") (name "unconnected-(IC3C-I_DIODE-Pad2)") (class "Default")
      (node (ref "IC3") (pin "2") (pinfunction "I_DIODE_2") (pintype "input"))
    )
    (net (code "66") (name "unconnected-(IC3D-I_DIODE-Pad15)") (class "Default")
      (node (ref "IC3") (pin "15") (pinfunction "I_DIODE_15") (pintype "input"))
    )
    (net (code "67") (name "unconnected-(IC8A-QD-Pad3)") (class "Default")
      (node (ref "IC8") (pin "3") (pinfunction "QD_3") (pintype "tri_state"))
    )
    (net (code "68") (name "unconnected-(IC8A-QE-Pad4)") (class "Default")
      (node (ref "IC8") (pin "4") (pinfunction "QE_4") (pintype "tri_state"))
    )
    (net (code "69") (name "unconnected-(IC8A-QF-Pad5)") (class "Default")
      (node (ref "IC8") (pin "5") (pinfunction "QF_5") (pintype "tri_state"))
    )
    (net (code "70") (name "unconnected-(IC8A-QG-Pad6)") (class "Default")
      (node (ref "IC8") (pin "6") (pinfunction "QG_6") (pintype "tri_state"))
    )
    (net (code "71") (name "unconnected-(IC8A-QH*-Pad9)") (class "Default")
      (node (ref "IC8") (pin "9") (pinfunction "QH*_9") (pintype "tri_state"))
    )
    (net (code "72") (name "unconnected-(IC8A-QH-Pad7)") (class "Default")
      (node (ref "IC8") (pin "7") (pinfunction "QH_7") (pintype "tri_state"))
    )
    (net (code "73") (name "unconnected-(IC9A-Y1-Pad1)") (class "Default")
      (node (ref "IC9") (pin "1") (pinfunction "Y1_1") (pintype "bidirectional"))
    )
    (net (code "74") (name "unconnected-(IC9A-Z1-Pad3)") (class "Default")
      (node (ref "IC9") (pin "3") (pinfunction "Z1_3") (pintype "bidirectional"))
    )
    (net (code "75") (name "unconnected-(J1-Pad2)") (class "Default")
      (node (ref "J1") (pin "2") (pinfunction "2_2") (pintype "passive"))
    )
    (net (code "76") (name "unconnected-(J3-PadTN)") (class "Default")
      (node (ref "J3") (pin "TN") (pinfunction "TN_TN") (pintype "passive"))
    )
    (net (code "77") (name "unconnected-(J4-Pad5)") (class "Default")
      (node (ref "J4") (pin "5") (pinfunction "5_5") (pintype "passive"))
    )
    (net (code "78") (name "unconnected-(J4-Pad6)") (class "Default")
      (node (ref "J4") (pin "6") (pinfunction "6_6") (pintype "passive"))
    )
    (net (code "79") (name "unconnected-(J6-Pad1)") (class "Default")
      (node (ref "J6") (pin "1") (pinfunction "1_1") (pintype "passive"))
    )
    (net (code "80") (name "unconnected-(J6-Pad6)") (class "Default")
      (node (ref "J6") (pin "6") (pinfunction "6_6") (pintype "passive"))
    )
  )
)
